# bigboard.net
KiCad netlist of a schematic drawn in EAGLE
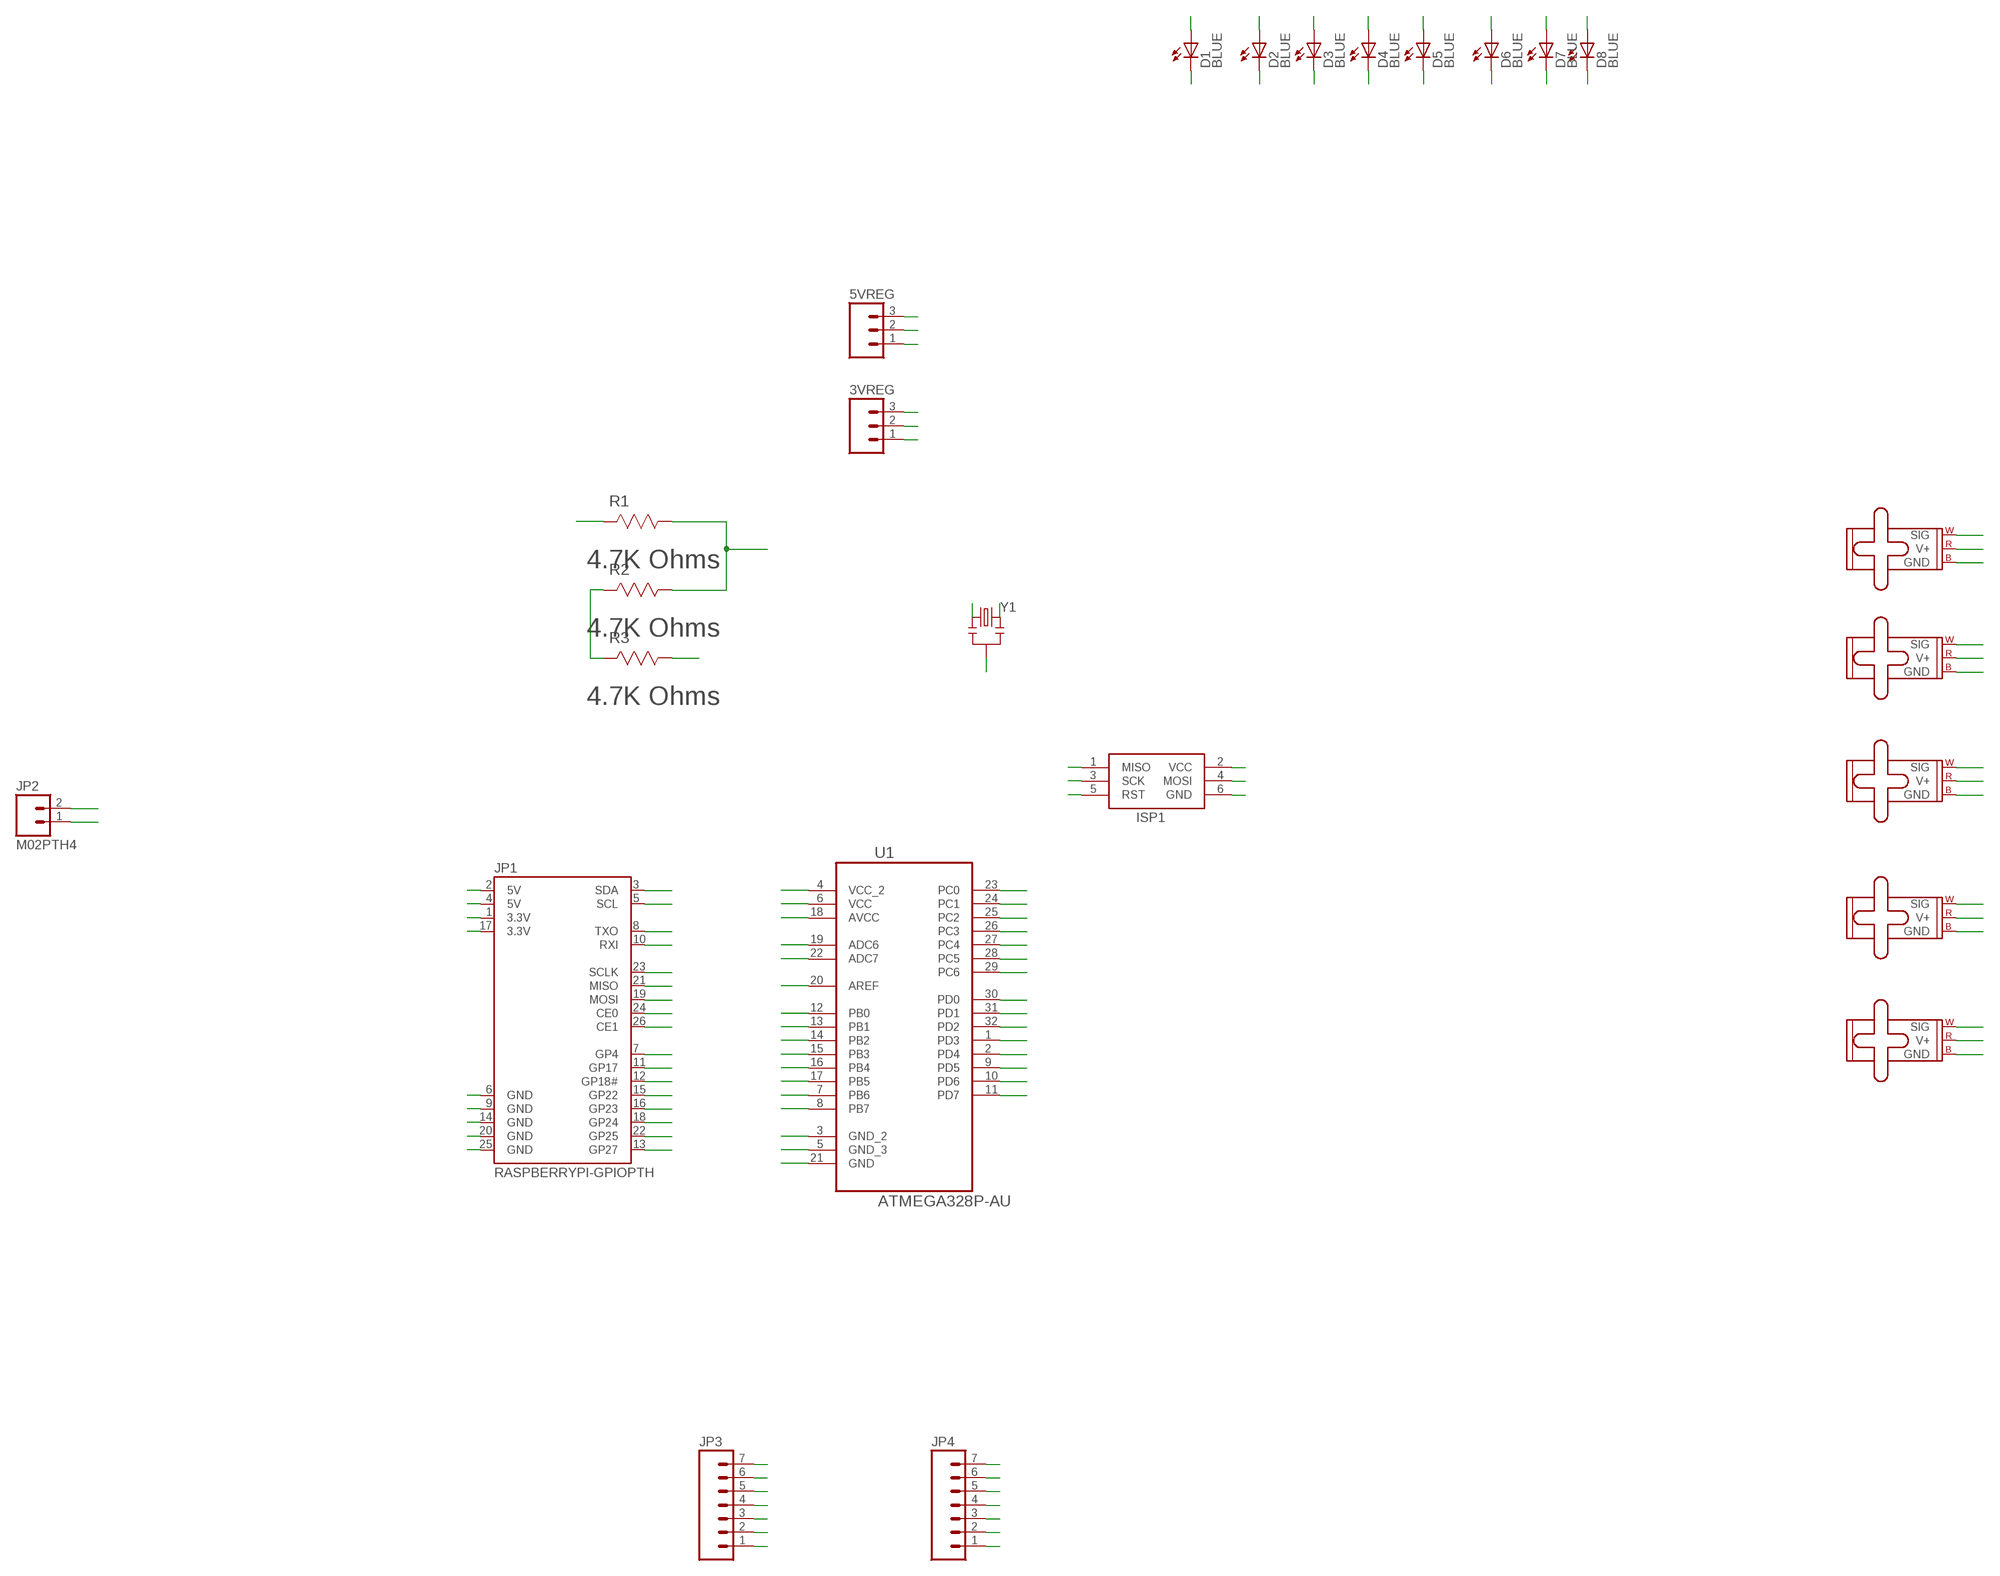
[diagram p0: schematic, sheet 1]

(export (version "E")
  (design (tool "Eeschema 10.0.6"))
  (components
    (comp (ref "3VREG")
      (value "M03PTH")
      (footprint "eagle-import:1X03")
      (libsource (lib "eagle-import") (part "M03PTH"))
    )
    (comp (ref "5VREG")
      (value "M03PTH")
      (footprint "eagle-import:1X03")
      (libsource (lib "eagle-import") (part "M03PTH"))
    )
    (comp (ref "D1")
      (value "BLUE")
      (footprint "eagle-import:LED-0603")
      (libsource (lib "eagle-import") (part "LED-BLUE0603"))
    )
    (comp (ref "D2")
      (value "BLUE")
      (footprint "eagle-import:LED-0603")
      (libsource (lib "eagle-import") (part "LED-BLUE0603"))
    )
    (comp (ref "D3")
      (value "BLUE")
      (footprint "eagle-import:LED-0603")
      (libsource (lib "eagle-import") (part "LED-BLUE0603"))
    )
    (comp (ref "D4")
      (value "BLUE")
      (footprint "eagle-import:LED-0603")
      (libsource (lib "eagle-import") (part "LED-BLUE0603"))
    )
    (comp (ref "D5")
      (value "BLUE")
      (footprint "eagle-import:LED-0603")
      (libsource (lib "eagle-import") (part "LED-BLUE0603"))
    )
    (comp (ref "D6")
      (value "BLUE")
      (footprint "eagle-import:LED-0603")
      (libsource (lib "eagle-import") (part "LED-BLUE0603"))
    )
    (comp (ref "D7")
      (value "BLUE")
      (footprint "eagle-import:LED-0603")
      (libsource (lib "eagle-import") (part "LED-BLUE0603"))
    )
    (comp (ref "D8")
      (value "BLUE")
      (footprint "eagle-import:LED-0603")
      (libsource (lib "eagle-import") (part "LED-BLUE0603"))
    )
    (comp (ref "ISP1")
      (value "AVRISP-6")
      (footprint "eagle-import:AVRISP")
      (libsource (lib "eagle-import") (part "AVRISP-6"))
    )
    (comp (ref "JP1")
      (value "RASPBERRYPI-GPIOPTH")
      (footprint "eagle-import:2X13-SHROUDED")
      (libsource (lib "eagle-import") (part "RASPBERRYPI-GPIOPTH"))
    )
    (comp (ref "JP2")
      (value "M02PTH4")
      (footprint "eagle-import:1X02_XTRA_BIG")
      (libsource (lib "eagle-import") (part "M02PTH4"))
    )
    (comp (ref "JP3")
      (value "M07")
      (footprint "eagle-import:1X07")
      (libsource (lib "eagle-import") (part "M07"))
    )
    (comp (ref "JP4")
      (value "M07")
      (footprint "eagle-import:1X07")
      (libsource (lib "eagle-import") (part "M07"))
    )
    (comp (ref "M1")
      (value "SMALL_SERVO")
      (footprint "eagle-import:1X03")
      (libsource (lib "eagle-import") (part "SMALL_SERVO"))
    )
    (comp (ref "M2")
      (value "SMALL_SERVO")
      (footprint "eagle-import:1X03")
      (libsource (lib "eagle-import") (part "SMALL_SERVO"))
    )
    (comp (ref "M3")
      (value "SMALL_SERVO")
      (footprint "eagle-import:1X03")
      (libsource (lib "eagle-import") (part "SMALL_SERVO"))
    )
    (comp (ref "M4")
      (value "SMALL_SERVO")
      (footprint "eagle-import:1X03")
      (libsource (lib "eagle-import") (part "SMALL_SERVO"))
    )
    (comp (ref "M5")
      (value "SMALL_SERVO")
      (footprint "eagle-import:1X03")
      (libsource (lib "eagle-import") (part "SMALL_SERVO"))
    )
    (comp (ref "R1")
      (value "4.7K Ohms")
      (footprint "eagle-import:RESC1608X60N")
      (fields (field (name "MPN") "CRCW06034K70FKEA") (field (name "TOLERANCE") "± 1.0 %"))
      (libsource (lib "eagle-import") (part "CRCW06034K70FKEA"))
    )
    (comp (ref "R2")
      (value "4.7K Ohms")
      (footprint "eagle-import:RESC1608X60N")
      (fields (field (name "MPN") "CRCW06034K70FKEA") (field (name "TOLERANCE") "± 1.0 %"))
      (libsource (lib "eagle-import") (part "CRCW06034K70FKEA"))
    )
    (comp (ref "R3")
      (value "4.7K Ohms")
      (footprint "eagle-import:RESC1608X60N")
      (fields (field (name "MPN") "CRCW06034K70FKEA") (field (name "TOLERANCE") "± 1.0 %"))
      (libsource (lib "eagle-import") (part "CRCW06034K70FKEA"))
    )
    (comp (ref "U1")
      (value "ATMEGA328P-AU")
      (footprint "eagle-import:QFP80P900X900X120-32N")
      (libsource (lib "eagle-import") (part "ATMEGA328P-AU"))
    )
    (comp (ref "Y1")
      (value "RESONATORPTH")
      (footprint "eagle-import:RESONATOR-PTH")
      (libsource (lib "eagle-import") (part "RESONATORPTH"))
    )
  )
  (nets
    (net (code "1") (name "/3V") (class "Default")
      (node (ref "3VREG") (pin "1") (pinfunction "1_1") (pintype "passive"))
      (node (ref "D8") (pin "A") (pinfunction "A_A") (pintype "passive"))
      (node (ref "JP1") (pin "1") (pinfunction "3.3V_1") (pintype "power_in"))
      (node (ref "JP1") (pin "17") (pinfunction "3.3V_17") (pintype "power_in"))
    )
    (net (code "2") (name "/5V") (class "Default")
      (node (ref "3VREG") (pin "3") (pinfunction "3_3") (pintype "passive"))
      (node (ref "5VREG") (pin "1") (pinfunction "1_1") (pintype "passive"))
      (node (ref "ISP1") (pin "2") (pinfunction "VCC_2") (pintype "power_in"))
      (node (ref "JP1") (pin "2") (pinfunction "5V_2") (pintype "power_in"))
      (node (ref "JP1") (pin "4") (pinfunction "5V_4") (pintype "power_in"))
      (node (ref "M1") (pin "2") (pinfunction "V+_2") (pintype "bidirectional"))
      (node (ref "M2") (pin "2") (pinfunction "V+_2") (pintype "bidirectional"))
      (node (ref "M3") (pin "2") (pinfunction "V+_2") (pintype "bidirectional"))
      (node (ref "M4") (pin "2") (pinfunction "V+_2") (pintype "bidirectional"))
      (node (ref "M5") (pin "2") (pinfunction "V+_2") (pintype "bidirectional"))
      (node (ref "U1") (pin "18") (pinfunction "AVCC_18") (pintype "power_in"))
      (node (ref "U1") (pin "4") (pinfunction "VCC_2_4") (pintype "power_in"))
      (node (ref "U1") (pin "6") (pinfunction "VCC_6") (pintype "power_in"))
    )
    (net (code "3") (name "/A0") (class "Default")
      (node (ref "JP3") (pin "1") (pinfunction "1_1") (pintype "passive"))
      (node (ref "U1") (pin "23") (pinfunction "PC0_23") (pintype "bidirectional"))
    )
    (net (code "4") (name "/A1") (class "Default")
      (node (ref "JP3") (pin "2") (pinfunction "2_2") (pintype "passive"))
      (node (ref "U1") (pin "24") (pinfunction "PC1_24") (pintype "bidirectional"))
    )
    (net (code "5") (name "/A2") (class "Default")
      (node (ref "JP3") (pin "3") (pinfunction "3_3") (pintype "passive"))
      (node (ref "U1") (pin "25") (pinfunction "PC2_25") (pintype "bidirectional"))
    )
    (net (code "6") (name "/A3") (class "Default")
      (node (ref "JP3") (pin "4") (pinfunction "4_4") (pintype "passive"))
      (node (ref "U1") (pin "26") (pinfunction "PC3_26") (pintype "bidirectional"))
    )
    (net (code "7") (name "/A4") (class "Default")
      (node (ref "JP3") (pin "5") (pinfunction "5_5") (pintype "passive"))
      (node (ref "U1") (pin "27") (pinfunction "PC4_27") (pintype "bidirectional"))
    )
    (net (code "8") (name "/A5") (class "Default")
      (node (ref "JP3") (pin "6") (pinfunction "6_6") (pintype "passive"))
      (node (ref "U1") (pin "28") (pinfunction "PC5_28") (pintype "bidirectional"))
    )
    (net (code "9") (name "/ARX") (class "Default")
      (node (ref "JP1") (pin "8") (pinfunction "TXO_8") (pintype "output"))
      (node (ref "U1") (pin "30") (pinfunction "PD0_30") (pintype "bidirectional"))
    )
    (net (code "10") (name "/ATX") (class "Default")
      (node (ref "R1") (pin "1") (pinfunction "R1_1") (pintype "passive"))
      (node (ref "R2") (pin "1") (pinfunction "R1_1") (pintype "passive"))
      (node (ref "U1") (pin "31") (pinfunction "PD1_31") (pintype "bidirectional"))
    )
    (net (code "11") (name "/D2") (class "Default")
      (node (ref "M1") (pin "1") (pinfunction "SIG_1") (pintype "bidirectional"))
      (node (ref "U1") (pin "32") (pinfunction "PD2_32") (pintype "bidirectional"))
    )
    (net (code "12") (name "/D3") (class "Default")
      (node (ref "M2") (pin "1") (pinfunction "SIG_1") (pintype "bidirectional"))
      (node (ref "U1") (pin "1") (pinfunction "PD3_1") (pintype "bidirectional"))
    )
    (net (code "13") (name "/D4") (class "Default")
      (node (ref "M3") (pin "1") (pinfunction "SIG_1") (pintype "bidirectional"))
      (node (ref "U1") (pin "2") (pinfunction "PD4_2") (pintype "bidirectional"))
    )
    (net (code "14") (name "/D5") (class "Default")
      (node (ref "M4") (pin "1") (pinfunction "SIG_1") (pintype "bidirectional"))
      (node (ref "U1") (pin "9") (pinfunction "PD5_9") (pintype "bidirectional"))
    )
    (net (code "15") (name "/D6") (class "Default")
      (node (ref "M5") (pin "1") (pinfunction "SIG_1") (pintype "bidirectional"))
      (node (ref "U1") (pin "10") (pinfunction "PD6_10") (pintype "bidirectional"))
    )
    (net (code "16") (name "/D7") (class "Default")
      (node (ref "D1") (pin "A") (pinfunction "A_A") (pintype "passive"))
      (node (ref "JP4") (pin "1") (pinfunction "1_1") (pintype "passive"))
      (node (ref "U1") (pin "11") (pinfunction "PD7_11") (pintype "bidirectional"))
    )
    (net (code "17") (name "/D8") (class "Default")
      (node (ref "D2") (pin "A") (pinfunction "A_A") (pintype "passive"))
      (node (ref "JP4") (pin "2") (pinfunction "2_2") (pintype "passive"))
      (node (ref "U1") (pin "12") (pinfunction "PB0_12") (pintype "bidirectional"))
    )
    (net (code "18") (name "/D9") (class "Default")
      (node (ref "D3") (pin "A") (pinfunction "A_A") (pintype "passive"))
      (node (ref "JP4") (pin "3") (pinfunction "3_3") (pintype "passive"))
      (node (ref "U1") (pin "13") (pinfunction "PB1_13") (pintype "bidirectional"))
    )
    (net (code "19") (name "/D10") (class "Default")
      (node (ref "D4") (pin "A") (pinfunction "A_A") (pintype "passive"))
      (node (ref "JP4") (pin "4") (pinfunction "4_4") (pintype "passive"))
      (node (ref "U1") (pin "14") (pinfunction "PB2_14") (pintype "bidirectional"))
    )
    (net (code "20") (name "/D11") (class "Default")
      (node (ref "D5") (pin "A") (pinfunction "A_A") (pintype "passive"))
      (node (ref "ISP1") (pin "4") (pinfunction "MOSI_4") (pintype "output"))
      (node (ref "JP4") (pin "5") (pinfunction "5_5") (pintype "passive"))
      (node (ref "U1") (pin "15") (pinfunction "PB3_15") (pintype "bidirectional"))
    )
    (net (code "21") (name "/D12") (class "Default")
      (node (ref "D6") (pin "A") (pinfunction "A_A") (pintype "passive"))
      (node (ref "ISP1") (pin "1") (pinfunction "MISO_1") (pintype "input"))
      (node (ref "JP4") (pin "6") (pinfunction "6_6") (pintype "passive"))
      (node (ref "U1") (pin "16") (pinfunction "PB4_16") (pintype "bidirectional"))
    )
    (net (code "22") (name "/D13") (class "Default")
      (node (ref "D7") (pin "A") (pinfunction "A_A") (pintype "passive"))
      (node (ref "ISP1") (pin "3") (pinfunction "SCK_3") (pintype "output"))
      (node (ref "JP4") (pin "7") (pinfunction "7_7") (pintype "passive"))
      (node (ref "U1") (pin "17") (pinfunction "PB5_17") (pintype "bidirectional"))
    )
    (net (code "23") (name "/GND") (class "Default")
      (node (ref "3VREG") (pin "2") (pinfunction "2_2") (pintype "passive"))
      (node (ref "5VREG") (pin "2") (pinfunction "2_2") (pintype "passive"))
      (node (ref "D1") (pin "C") (pinfunction "C_C") (pintype "passive"))
      (node (ref "D2") (pin "C") (pinfunction "C_C") (pintype "passive"))
      (node (ref "D3") (pin "C") (pinfunction "C_C") (pintype "passive"))
      (node (ref "D4") (pin "C") (pinfunction "C_C") (pintype "passive"))
      (node (ref "D5") (pin "C") (pinfunction "C_C") (pintype "passive"))
      (node (ref "D6") (pin "C") (pinfunction "C_C") (pintype "passive"))
      (node (ref "D7") (pin "C") (pinfunction "C_C") (pintype "passive"))
      (node (ref "D8") (pin "C") (pinfunction "C_C") (pintype "passive"))
      (node (ref "ISP1") (pin "6") (pinfunction "GND_6") (pintype "power_in"))
      (node (ref "JP1") (pin "14") (pinfunction "GND_14") (pintype "power_in"))
      (node (ref "JP1") (pin "20") (pinfunction "GND_20") (pintype "power_in"))
      (node (ref "JP1") (pin "25") (pinfunction "GND_25") (pintype "power_in"))
      (node (ref "JP1") (pin "6") (pinfunction "GND_6") (pintype "power_in"))
      (node (ref "JP1") (pin "9") (pinfunction "GND_9") (pintype "power_in"))
      (node (ref "JP2") (pin "2") (pinfunction "2_2") (pintype "passive"))
      (node (ref "JP3") (pin "7") (pinfunction "7_7") (pintype "passive"))
      (node (ref "M1") (pin "3") (pinfunction "GND_3") (pintype "bidirectional"))
      (node (ref "M2") (pin "3") (pinfunction "GND_3") (pintype "bidirectional"))
      (node (ref "M3") (pin "3") (pinfunction "GND_3") (pintype "bidirectional"))
      (node (ref "M4") (pin "3") (pinfunction "GND_3") (pintype "bidirectional"))
      (node (ref "M5") (pin "3") (pinfunction "GND_3") (pintype "bidirectional"))
      (node (ref "R3") (pin "1") (pinfunction "R1_1") (pintype "passive"))
      (node (ref "U1") (pin "21") (pinfunction "GND_21") (pintype "passive"))
      (node (ref "U1") (pin "3") (pinfunction "GND_2_3") (pintype "passive"))
      (node (ref "U1") (pin "5") (pinfunction "GND_3_5") (pintype "passive"))
      (node (ref "Y1") (pin "2") (pinfunction "2_2") (pintype "passive"))
    )
    (net (code "24") (name "/RESET") (class "Default")
      (node (ref "ISP1") (pin "5") (pinfunction "RST_5") (pintype "output"))
      (node (ref "U1") (pin "29") (pinfunction "PC6_29") (pintype "bidirectional"))
    )
    (net (code "25") (name "/RRX") (class "Default")
      (node (ref "JP1") (pin "10") (pinfunction "RXI_10") (pintype "input"))
      (node (ref "R1") (pin "2") (pinfunction "R2_2") (pintype "passive"))
    )
    (net (code "26") (name "/VIN") (class "Default")
      (node (ref "5VREG") (pin "3") (pinfunction "3_3") (pintype "passive"))
      (node (ref "JP2") (pin "1") (pinfunction "1_1") (pintype "passive"))
    )
    (net (code "27") (name "/XTAL1") (class "Default")
      (node (ref "U1") (pin "7") (pinfunction "PB6_7") (pintype "bidirectional"))
      (node (ref "Y1") (pin "1") (pinfunction "1_1") (pintype "passive"))
    )
    (net (code "28") (name "/XTAL2") (class "Default")
      (node (ref "U1") (pin "8") (pinfunction "PB7_8") (pintype "bidirectional"))
      (node (ref "Y1") (pin "3") (pinfunction "3_3") (pintype "passive"))
    )
    (net (code "29") (name "Net-(R2-R2)") (class "Default")
      (node (ref "R2") (pin "2") (pinfunction "R2_2") (pintype "passive"))
      (node (ref "R3") (pin "2") (pinfunction "R2_2") (pintype "passive"))
    )
    (net (code "30") (name "unconnected-(JP1-CE0-Pad24)") (class "Default")
      (node (ref "JP1") (pin "24") (pinfunction "CE0_24") (pintype "output"))
    )
    (net (code "31") (name "unconnected-(JP1-CE1-Pad26)") (class "Default")
      (node (ref "JP1") (pin "26") (pinfunction "CE1_26") (pintype "output"))
    )
    (net (code "32") (name "unconnected-(JP1-GP4-Pad7)") (class "Default")
      (node (ref "JP1") (pin "7") (pinfunction "GP4_7") (pintype "bidirectional"))
    )
    (net (code "33") (name "unconnected-(JP1-GP17-Pad11)") (class "Default")
      (node (ref "JP1") (pin "11") (pinfunction "GP17_11") (pintype "bidirectional"))
    )
    (net (code "34") (name "unconnected-(JP1-GP18#-Pad12)") (class "Default")
      (node (ref "JP1") (pin "12") (pinfunction "GP18#_12") (pintype "bidirectional"))
    )
    (net (code "35") (name "unconnected-(JP1-GP22-Pad15)") (class "Default")
      (node (ref "JP1") (pin "15") (pinfunction "GP22_15") (pintype "bidirectional"))
    )
    (net (code "36") (name "unconnected-(JP1-GP23-Pad16)") (class "Default")
      (node (ref "JP1") (pin "16") (pinfunction "GP23_16") (pintype "bidirectional"))
    )
    (net (code "37") (name "unconnected-(JP1-GP24-Pad18)") (class "Default")
      (node (ref "JP1") (pin "18") (pinfunction "GP24_18") (pintype "bidirectional"))
    )
    (net (code "38") (name "unconnected-(JP1-GP25-Pad22)") (class "Default")
      (node (ref "JP1") (pin "22") (pinfunction "GP25_22") (pintype "bidirectional"))
    )
    (net (code "39") (name "unconnected-(JP1-GP27-Pad13)") (class "Default")
      (node (ref "JP1") (pin "13") (pinfunction "GP27_13") (pintype "bidirectional"))
    )
    (net (code "40") (name "unconnected-(JP1-MISO-Pad21)") (class "Default")
      (node (ref "JP1") (pin "21") (pinfunction "MISO_21") (pintype "input"))
    )
    (net (code "41") (name "unconnected-(JP1-MOSI-Pad19)") (class "Default")
      (node (ref "JP1") (pin "19") (pinfunction "MOSI_19") (pintype "output"))
    )
    (net (code "42") (name "unconnected-(JP1-SCL-Pad5)") (class "Default")
      (node (ref "JP1") (pin "5") (pinfunction "SCL_5") (pintype "bidirectional"))
    )
    (net (code "43") (name "unconnected-(JP1-SCLK-Pad23)") (class "Default")
      (node (ref "JP1") (pin "23") (pinfunction "SCLK_23") (pintype "output"))
    )
    (net (code "44") (name "unconnected-(JP1-SDA-Pad3)") (class "Default")
      (node (ref "JP1") (pin "3") (pinfunction "SDA_3") (pintype "bidirectional"))
    )
    (net (code "45") (name "unconnected-(U1-ADC6-Pad19)") (class "Default")
      (node (ref "U1") (pin "19") (pinfunction "ADC6_19") (pintype "input"))
    )
    (net (code "46") (name "unconnected-(U1-ADC7-Pad22)") (class "Default")
      (node (ref "U1") (pin "22") (pinfunction "ADC7_22") (pintype "input"))
    )
    (net (code "47") (name "unconnected-(U1-AREF-Pad20)") (class "Default")
      (node (ref "U1") (pin "20") (pinfunction "AREF_20") (pintype "input"))
    )
  )
)
